# Power_Regulation.net
KiCad netlist of a schematic drawn in Altium Designer
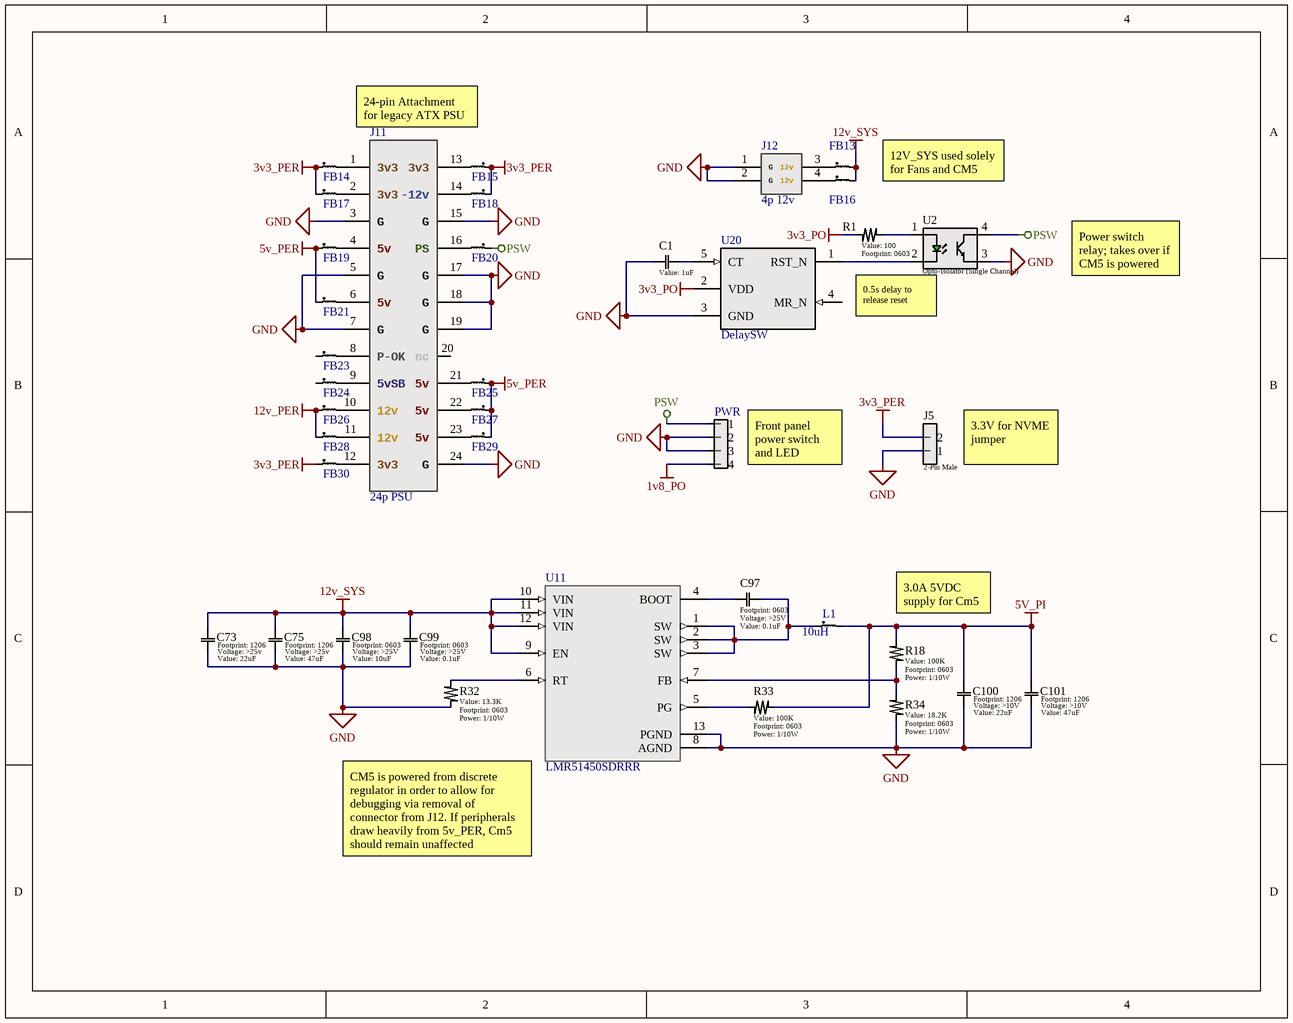
[diagram p0: Power_Regulation.SchDoc]

(export (version "E")
  (design (tool "Eeschema 10.0.6"))
  (components
    (comp (ref "C1")
      (value "1uF")
      (footprint "0603")
      (fields
        (field (name "VOLTAGE") "10V")
        (field (name "TOLERANCE") "10%")
        (field (name "Comment") "Generic Capacitor")
      )
      (libsource (lib "Capacitors") (part "Generic Capacitor"))
    )
    (comp (ref "C73")
      (value "22uF")
      (footprint "1206")
      (fields
        (field (name "VOLTAGE") ">25v")
        (field (name "TOLERANCE") "20%")
        (field (name "Comment") "Generic Capacitor")
      )
      (libsource (lib "Capacitors") (part "Generic Capacitor"))
    )
    (comp (ref "C75")
      (value "47uF")
      (footprint "1206")
      (fields
        (field (name "VOLTAGE") ">25v")
        (field (name "TOLERANCE") "20%")
        (field (name "Comment") "Generic Capacitor")
      )
      (libsource (lib "Capacitors") (part "Generic Capacitor"))
    )
    (comp (ref "C97")
      (value "0.1uF")
      (footprint "0603")
      (fields
        (field (name "VOLTAGE") ">25V")
        (field (name "TOLERANCE") "10%")
        (field (name "Comment") "Generic Capacitor")
      )
      (libsource (lib "Capacitors") (part "Generic Capacitor"))
    )
    (comp (ref "C98")
      (value "10uF")
      (footprint "0603")
      (fields
        (field (name "VOLTAGE") ">25V")
        (field (name "TOLERANCE") "10%")
        (field (name "Comment") "Generic Capacitor")
      )
      (libsource (lib "Capacitors") (part "Generic Capacitor"))
    )
    (comp (ref "C99")
      (value "0.1uF")
      (footprint "0603")
      (fields
        (field (name "VOLTAGE") ">25V")
        (field (name "TOLERANCE") "10%")
        (field (name "Comment") "Generic Capacitor")
      )
      (libsource (lib "Capacitors") (part "Generic Capacitor"))
    )
    (comp (ref "C100")
      (value "22uF")
      (footprint "1206")
      (fields
        (field (name "VOLTAGE") ">10V")
        (field (name "TOLERANCE") "20%")
        (field (name "Comment") "Generic Capacitor")
      )
      (libsource (lib "Capacitors") (part "Generic Capacitor"))
    )
    (comp (ref "C101")
      (value "47uF")
      (footprint "1206")
      (fields
        (field (name "VOLTAGE") ">10V")
        (field (name "TOLERANCE") "10%")
        (field (name "Comment") "Generic Capacitor")
      )
      (libsource (lib "Capacitors") (part "Generic Capacitor"))
    )
    (comp (ref "FB13")
      (value "1206 Ferrite")
      (footprint "1206")
      (description "160 Ohms @ 100MHz 1 Power, Signal Line Ferrite Bead 1206 (3216 Metric) 6A 18mOhm")
      (libsource (lib "Inductors") (part "HI1206T161R-10"))
    )
    (comp (ref "FB14")
      (value "1206 Ferrite")
      (footprint "1206")
      (description "160 Ohms @ 100MHz 1 Power, Signal Line Ferrite Bead 1206 (3216 Metric) 6A 18mOhm")
      (libsource (lib "Inductors") (part "HI1206T161R-10"))
    )
    (comp (ref "FB15")
      (value "1206 Ferrite")
      (footprint "1206")
      (description "160 Ohms @ 100MHz 1 Power, Signal Line Ferrite Bead 1206 (3216 Metric) 6A 18mOhm")
      (libsource (lib "") (part "HI1206T161R-10_1"))
    )
    (comp (ref "FB16")
      (value "1206 Ferrite")
      (footprint "1206")
      (description "160 Ohms @ 100MHz 1 Power, Signal Line Ferrite Bead 1206 (3216 Metric) 6A 18mOhm")
      (libsource (lib "Inductors") (part "HI1206T161R-10"))
    )
    (comp (ref "FB17")
      (value "1206 Ferrite")
      (footprint "1206")
      (description "160 Ohms @ 100MHz 1 Power, Signal Line Ferrite Bead 1206 (3216 Metric) 6A 18mOhm")
      (libsource (lib "Inductors") (part "HI1206T161R-10"))
    )
    (comp (ref "FB18")
      (value "1206 Ferrite")
      (footprint "1206")
      (description "160 Ohms @ 100MHz 1 Power, Signal Line Ferrite Bead 1206 (3216 Metric) 6A 18mOhm")
      (libsource (lib "") (part "HI1206T161R-10_1"))
    )
    (comp (ref "FB19")
      (value "1206 Ferrite")
      (footprint "1206")
      (description "160 Ohms @ 100MHz 1 Power, Signal Line Ferrite Bead 1206 (3216 Metric) 6A 18mOhm")
      (libsource (lib "Inductors") (part "HI1206T161R-10"))
    )
    (comp (ref "FB20")
      (value "1206 Ferrite")
      (footprint "1206")
      (description "160 Ohms @ 100MHz 1 Power, Signal Line Ferrite Bead 1206 (3216 Metric) 6A 18mOhm")
      (libsource (lib "") (part "HI1206T161R-10_1"))
    )
    (comp (ref "FB21")
      (value "1206 Ferrite")
      (footprint "1206")
      (description "160 Ohms @ 100MHz 1 Power, Signal Line Ferrite Bead 1206 (3216 Metric) 6A 18mOhm")
      (libsource (lib "Inductors") (part "HI1206T161R-10"))
    )
    (comp (ref "FB23")
      (value "1206 Ferrite")
      (footprint "1206")
      (description "160 Ohms @ 100MHz 1 Power, Signal Line Ferrite Bead 1206 (3216 Metric) 6A 18mOhm")
      (libsource (lib "Inductors") (part "HI1206T161R-10"))
    )
    (comp (ref "FB24")
      (value "1206 Ferrite")
      (footprint "1206")
      (description "160 Ohms @ 100MHz 1 Power, Signal Line Ferrite Bead 1206 (3216 Metric) 6A 18mOhm")
      (libsource (lib "Inductors") (part "HI1206T161R-10"))
    )
    (comp (ref "FB25")
      (value "1206 Ferrite")
      (footprint "1206")
      (description "160 Ohms @ 100MHz 1 Power, Signal Line Ferrite Bead 1206 (3216 Metric) 6A 18mOhm")
      (libsource (lib "") (part "HI1206T161R-10_1"))
    )
    (comp (ref "FB26")
      (value "1206 Ferrite")
      (footprint "1206")
      (description "160 Ohms @ 100MHz 1 Power, Signal Line Ferrite Bead 1206 (3216 Metric) 6A 18mOhm")
      (libsource (lib "Inductors") (part "HI1206T161R-10"))
    )
    (comp (ref "FB27")
      (value "1206 Ferrite")
      (footprint "1206")
      (description "160 Ohms @ 100MHz 1 Power, Signal Line Ferrite Bead 1206 (3216 Metric) 6A 18mOhm")
      (libsource (lib "") (part "HI1206T161R-10_1"))
    )
    (comp (ref "FB28")
      (value "1206 Ferrite")
      (footprint "1206")
      (description "160 Ohms @ 100MHz 1 Power, Signal Line Ferrite Bead 1206 (3216 Metric) 6A 18mOhm")
      (libsource (lib "Inductors") (part "HI1206T161R-10"))
    )
    (comp (ref "FB29")
      (value "1206 Ferrite")
      (footprint "1206")
      (description "160 Ohms @ 100MHz 1 Power, Signal Line Ferrite Bead 1206 (3216 Metric) 6A 18mOhm")
      (libsource (lib "") (part "HI1206T161R-10_1"))
    )
    (comp (ref "FB30")
      (value "1206 Ferrite")
      (footprint "1206")
      (description "160 Ohms @ 100MHz 1 Power, Signal Line Ferrite Bead 1206 (3216 Metric) 6A 18mOhm")
      (libsource (lib "Inductors") (part "HI1206T161R-10"))
    )
    (comp (ref "J5")
      (value "2-Pin Male")
      (footprint "0022057025")
      (description "Conn Shrouded Header (4 Sides) HDR 2 POS 2.5mm Solder RA Thru-Hole SPOX™ Bag")
      (libsource (lib "Connectors") (part "0022057025"))
    )
    (comp (ref "J11")
      (value "24p PSU")
      (footprint "CONN_442060007_MOL")
      (description "Connector Header Through Hole 24 position 0.165\" (4.20mm)")
      (libsource (lib "Connectors") (part "442060007"))
    )
    (comp (ref "J12")
      (value "4p 12v")
      (footprint "CON_39281043")
      (description "Connector Header Through Hole 4 position 0.165\" (4.20mm)")
      (libsource (lib "Connectors") (part "39281043"))
    )
    (comp (ref "L1")
      (value "10uH")
      (footprint "SMD 8.2x8.6mm")
      (description "5.1A 10uH ±20% 5.2A - Power Inductor")
      (fields
        (field (name "MANUFACTURER_PART_NUMBER") "IHLP3232DZER100M5A")
        (field (name "COPYRIGHT") "Copyright (C) 2023 Ultra Librarian. All rights reserved.")
      )
      (libsource (lib "Inductors") (part "IHLP3232DZER100M5A"))
    )
    (comp (ref "PWR")
      (value "4-Pin Male Header (0.100\" Pitch)")
      (footprint "TSW-104-07-T-S")
      (description "Connector Header Through Hole 4 position 0.100\" (2.54mm)")
      (libsource (lib "Connectors") (part "TSW-104-07-T-S"))
    )
    (comp (ref "R1")
      (value "100")
      (footprint "0603")
      (fields
        (field (name "TOLERANCE") "1%")
        (field (name "POWER") "1/10W")
        (field (name "Comment") "Generic Resistor")
      )
      (libsource (lib "Resistors") (part "Generic Resistor"))
    )
    (comp (ref "R18")
      (value "100K")
      (footprint "0603")
      (fields
        (field (name "TOLERANCE") "1%")
        (field (name "POWER") "1/10W")
        (field (name "Comment") "Generic Resistor")
      )
      (libsource (lib "Resistors") (part "Generic Resistor"))
    )
    (comp (ref "R32")
      (value "13.3K")
      (footprint "0603")
      (fields
        (field (name "TOLERANCE") "1%")
        (field (name "POWER") "1/10W")
        (field (name "Comment") "Generic Resistor")
      )
      (libsource (lib "Resistors") (part "Generic Resistor"))
    )
    (comp (ref "R33")
      (value "100K")
      (footprint "0603")
      (fields
        (field (name "TOLERANCE") "1%")
        (field (name "POWER") "1/10W")
        (field (name "Comment") "Generic Resistor")
      )
      (libsource (lib "Resistors") (part "Generic Resistor"))
    )
    (comp (ref "R34")
      (value "18.2K")
      (footprint "0603")
      (fields
        (field (name "TOLERANCE") "1%")
        (field (name "POWER") "1/10W")
        (field (name "Comment") "Generic Resistor")
      )
      (libsource (lib "Resistors") (part "Generic Resistor"))
    )
    (comp (ref "U2")
      (value "Opto-Isolator (Single Channel)")
      (footprint "4-SMD (7.62mm Gull-Wing) Opto-Transistor")
      (description "LTV Series Single Channel 80 V 5000 Vrms Transistor Output Optocoupler SMT-DIP-4")
      (fields
        (field (name "MANUFACTURER") "Vishay Lite-On")
        (field (name "MANUFACTURER PART NUMBER") "LTV-816S-TA1")
      )
      (libsource (lib "Switches") (part "LTV-816S"))
    )
    (comp (ref "U11")
      (value "LMR51450SDRRR")
      (footprint "WSON-12")
      (description "36-V, 5-A synchronous buck converter")
      (fields (field (name "MF") "Texas Instruments"))
      (libsource (lib "Regulators") (part "LMR51450SDRRR"))
    )
    (comp (ref "U20")
      (value "DelaySW")
      (footprint "TSOT-23-5")
      (description "Supervisor Open Drain or Open Collector 1 Channel SOT-23-5\r\n2.2V Threshold")
      (libsource (lib "Switches") (part "TPS3840DL22DBVR"))
    )
  )
  (nets
    (net (code "1") (name "1v8_PO") (class "Default")
      (node (ref "PWR") (pin "4") (pinfunction "4_4") (pintype "passive"))
    )
    (net (code "2") (name "3v3_PER") (class "Default")
      (node (ref "FB14") (pin "1") (pinfunction "1_1") (pintype "passive"))
      (node (ref "FB15") (pin "1") (pinfunction "1_1") (pintype "passive"))
      (node (ref "FB17") (pin "1") (pinfunction "1_1") (pintype "passive"))
      (node (ref "FB18") (pin "1") (pinfunction "1_1") (pintype "passive"))
      (node (ref "FB30") (pin "1") (pinfunction "1_1") (pintype "passive"))
      (node (ref "J5") (pin "2") (pinfunction "2_2") (pintype "passive"))
    )
    (net (code "3") (name "3v3_PO") (class "Default")
      (node (ref "R1") (pin "1") (pinfunction "1_1") (pintype "passive"))
      (node (ref "U20") (pin "2") (pinfunction "VDD_2") (pintype "power_in"))
    )
    (net (code "4") (name "5V_PI") (class "Default")
      (node (ref "C100") (pin "1") (pinfunction "1_1") (pintype "passive"))
      (node (ref "C101") (pin "1") (pinfunction "1_1") (pintype "passive"))
      (node (ref "L1") (pin "2") (pinfunction "2_2") (pintype "passive"))
      (node (ref "R18") (pin "2") (pinfunction "2_2") (pintype "passive"))
      (node (ref "R33") (pin "1") (pinfunction "1_1") (pintype "passive"))
    )
    (net (code "5") (name "5v_PER") (class "Default")
      (node (ref "FB19") (pin "1") (pinfunction "1_1") (pintype "passive"))
      (node (ref "FB21") (pin "1") (pinfunction "1_1") (pintype "passive"))
      (node (ref "FB25") (pin "1") (pinfunction "1_1") (pintype "passive"))
      (node (ref "FB27") (pin "1") (pinfunction "1_1") (pintype "passive"))
      (node (ref "FB29") (pin "1") (pinfunction "1_1") (pintype "passive"))
    )
    (net (code "6") (name "12v_PER") (class "Default")
      (node (ref "FB26") (pin "1") (pinfunction "1_1") (pintype "passive"))
      (node (ref "FB28") (pin "1") (pinfunction "1_1") (pintype "passive"))
    )
    (net (code "7") (name "12v_SYS") (class "Default")
      (node (ref "C73") (pin "1") (pinfunction "1_1") (pintype "passive"))
      (node (ref "C75") (pin "1") (pinfunction "1_1") (pintype "passive"))
      (node (ref "C98") (pin "1") (pinfunction "1_1") (pintype "passive"))
      (node (ref "C99") (pin "1") (pinfunction "1_1") (pintype "passive"))
      (node (ref "FB13") (pin "2") (pinfunction "2_2") (pintype "passive"))
      (node (ref "FB16") (pin "2") (pinfunction "2_2") (pintype "passive"))
      (node (ref "U11") (pin "10") (pinfunction "VIN_10") (pintype "input"))
      (node (ref "U11") (pin "11") (pinfunction "VIN_11") (pintype "input"))
      (node (ref "U11") (pin "12") (pinfunction "VIN_12") (pintype "input"))
      (node (ref "U11") (pin "9") (pinfunction "EN_9") (pintype "input"))
    )
    (net (code "8") (name "GND") (class "Default")
      (node (ref "C1") (pin "2") (pinfunction "2_2") (pintype "passive"))
      (node (ref "C100") (pin "2") (pinfunction "2_2") (pintype "passive"))
      (node (ref "C101") (pin "2") (pinfunction "2_2") (pintype "passive"))
      (node (ref "C73") (pin "2") (pinfunction "2_2") (pintype "passive"))
      (node (ref "C75") (pin "2") (pinfunction "2_2") (pintype "passive"))
      (node (ref "C98") (pin "2") (pinfunction "2_2") (pintype "passive"))
      (node (ref "C99") (pin "2") (pinfunction "2_2") (pintype "passive"))
      (node (ref "J11") (pin "15") (pinfunction "G_15") (pintype "passive"))
      (node (ref "J11") (pin "17") (pinfunction "G_17") (pintype "passive"))
      (node (ref "J11") (pin "18") (pinfunction "G_18") (pintype "passive"))
      (node (ref "J11") (pin "19") (pinfunction "G_19") (pintype "passive"))
      (node (ref "J11") (pin "24") (pinfunction "G_24") (pintype "passive"))
      (node (ref "J11") (pin "3") (pinfunction "G_3") (pintype "passive"))
      (node (ref "J11") (pin "5") (pinfunction "G_5") (pintype "passive"))
      (node (ref "J11") (pin "7") (pinfunction "G_7") (pintype "passive"))
      (node (ref "J12") (pin "1") (pinfunction "G_1") (pintype "passive"))
      (node (ref "J12") (pin "2") (pinfunction "G_2") (pintype "passive"))
      (node (ref "J5") (pin "1") (pinfunction "1_1") (pintype "passive"))
      (node (ref "PWR") (pin "2") (pinfunction "2_2") (pintype "passive"))
      (node (ref "PWR") (pin "3") (pinfunction "3_3") (pintype "passive"))
      (node (ref "R32") (pin "1") (pinfunction "1_1") (pintype "passive"))
      (node (ref "R34") (pin "1") (pinfunction "1_1") (pintype "passive"))
      (node (ref "U11") (pin "13") (pinfunction "PGND_13") (pintype "power_in"))
      (node (ref "U11") (pin "8") (pinfunction "AGND_8") (pintype "power_in"))
      (node (ref "U2") (pin "3") (pinfunction "3_3") (pintype "passive"))
      (node (ref "U20") (pin "3") (pinfunction "GND_3") (pintype "power_in"))
    )
    (net (code "9") (name "Net-(C97-Pad2)") (class "Default")
      (node (ref "C97") (pin "2") (pinfunction "2_2") (pintype "passive"))
      (node (ref "L1") (pin "1") (pinfunction "1_1") (pintype "passive"))
      (node (ref "U11") (pin "1") (pinfunction "SW_1") (pintype "output"))
      (node (ref "U11") (pin "2") (pinfunction "SW_2") (pintype "output"))
      (node (ref "U11") (pin "3") (pinfunction "SW_3") (pintype "output"))
    )
    (net (code "10") (name "Net-(FB13-Pad1)") (class "Default")
      (node (ref "FB13") (pin "1") (pinfunction "1_1") (pintype "passive"))
      (node (ref "J12") (pin "3") (pinfunction "12v_3") (pintype "passive"))
    )
    (net (code "11") (name "Net-(FB14-Pad2)") (class "Default")
      (node (ref "FB14") (pin "2") (pinfunction "2_2") (pintype "passive"))
      (node (ref "J11") (pin "1") (pinfunction "3v3_1") (pintype "passive"))
    )
    (net (code "12") (name "Net-(FB15-Pad2)") (class "Default")
      (node (ref "FB15") (pin "2") (pinfunction "2_2") (pintype "passive"))
      (node (ref "J11") (pin "13") (pinfunction "3v3_13") (pintype "passive"))
    )
    (net (code "13") (name "Net-(FB16-Pad1)") (class "Default")
      (node (ref "FB16") (pin "1") (pinfunction "1_1") (pintype "passive"))
      (node (ref "J12") (pin "4") (pinfunction "12v_4") (pintype "passive"))
    )
    (net (code "14") (name "Net-(FB17-Pad2)") (class "Default")
      (node (ref "FB17") (pin "2") (pinfunction "2_2") (pintype "passive"))
      (node (ref "J11") (pin "2") (pinfunction "3v3_2") (pintype "passive"))
    )
    (net (code "15") (name "Net-(FB19-Pad2)") (class "Default")
      (node (ref "FB19") (pin "2") (pinfunction "2_2") (pintype "passive"))
      (node (ref "J11") (pin "4") (pinfunction "5v_4") (pintype "passive"))
    )
    (net (code "16") (name "Net-(FB21-Pad2)") (class "Default")
      (node (ref "FB21") (pin "2") (pinfunction "2_2") (pintype "passive"))
      (node (ref "J11") (pin "6") (pinfunction "5v_6") (pintype "passive"))
    )
    (net (code "17") (name "Net-(FB25-Pad2)") (class "Default")
      (node (ref "FB25") (pin "2") (pinfunction "2_2") (pintype "passive"))
      (node (ref "J11") (pin "21") (pinfunction "5v_21") (pintype "passive"))
    )
    (net (code "18") (name "Net-(FB26-Pad2)") (class "Default")
      (node (ref "FB26") (pin "2") (pinfunction "2_2") (pintype "passive"))
      (node (ref "J11") (pin "10") (pinfunction "12v_10") (pintype "passive"))
    )
    (net (code "19") (name "Net-(FB27-Pad2)") (class "Default")
      (node (ref "FB27") (pin "2") (pinfunction "2_2") (pintype "passive"))
      (node (ref "J11") (pin "22") (pinfunction "5v_22") (pintype "passive"))
    )
    (net (code "20") (name "Net-(FB28-Pad2)") (class "Default")
      (node (ref "FB28") (pin "2") (pinfunction "2_2") (pintype "passive"))
      (node (ref "J11") (pin "11") (pinfunction "12v_11") (pintype "passive"))
    )
    (net (code "21") (name "Net-(FB29-Pad2)") (class "Default")
      (node (ref "FB29") (pin "2") (pinfunction "2_2") (pintype "passive"))
      (node (ref "J11") (pin "23") (pinfunction "5v_23") (pintype "passive"))
    )
    (net (code "22") (name "Net-(FB30-Pad2)") (class "Default")
      (node (ref "FB30") (pin "2") (pinfunction "2_2") (pintype "passive"))
      (node (ref "J11") (pin "12") (pinfunction "3v3_12") (pintype "passive"))
    )
    (net (code "23") (name "Net-(J11--12v)") (class "Default")
      (node (ref "FB18") (pin "2") (pinfunction "2_2") (pintype "passive"))
      (node (ref "J11") (pin "14") (pinfunction "-12v_14") (pintype "passive"))
    )
    (net (code "24") (name "Net-(J11-5vSB)") (class "Default")
      (node (ref "FB24") (pin "2") (pinfunction "2_2") (pintype "passive"))
      (node (ref "J11") (pin "9") (pinfunction "5vSB_9") (pintype "passive"))
    )
    (net (code "25") (name "Net-(J11-P-OK)") (class "Default")
      (node (ref "FB23") (pin "2") (pinfunction "2_2") (pintype "passive"))
      (node (ref "J11") (pin "8") (pinfunction "P-OK_8") (pintype "passive"))
    )
    (net (code "26") (name "Net-(J11-PS)") (class "Default")
      (node (ref "FB20") (pin "2") (pinfunction "2_2") (pintype "passive"))
      (node (ref "J11") (pin "16") (pinfunction "PS_16") (pintype "passive"))
    )
    (net (code "27") (name "Net-(R1-Pad2)") (class "Default")
      (node (ref "R1") (pin "2") (pinfunction "2_2") (pintype "passive"))
      (node (ref "U2") (pin "1") (pinfunction "1_1") (pintype "passive"))
    )
    (net (code "28") (name "Net-(U11-BOOT)") (class "Default")
      (node (ref "C97") (pin "1") (pinfunction "1_1") (pintype "passive"))
      (node (ref "U11") (pin "4") (pinfunction "BOOT_4") (pintype "passive"))
    )
    (net (code "29") (name "Net-(U11-FB)") (class "Default")
      (node (ref "R18") (pin "1") (pinfunction "1_1") (pintype "passive"))
      (node (ref "R34") (pin "2") (pinfunction "2_2") (pintype "passive"))
      (node (ref "U11") (pin "7") (pinfunction "FB_7") (pintype "input"))
    )
    (net (code "30") (name "Net-(U11-PG)") (class "Default")
      (node (ref "R33") (pin "2") (pinfunction "2_2") (pintype "passive"))
      (node (ref "U11") (pin "5") (pinfunction "PG_5") (pintype "output"))
    )
    (net (code "31") (name "Net-(U11-RT)") (class "Default")
      (node (ref "R32") (pin "2") (pinfunction "2_2") (pintype "passive"))
      (node (ref "U11") (pin "6") (pinfunction "RT_6") (pintype "input"))
    )
    (net (code "32") (name "Net-(U20-CT)") (class "Default")
      (node (ref "C1") (pin "1") (pinfunction "1_1") (pintype "passive"))
      (node (ref "U20") (pin "5") (pinfunction "CT_5") (pintype "input"))
    )
    (net (code "33") (name "Net-(U20-RST_N)") (class "Default")
      (node (ref "U2") (pin "2") (pinfunction "2_2") (pintype "passive"))
      (node (ref "U20") (pin "1") (pinfunction "RST_N_1") (pintype "open_collector"))
    )
    (net (code "34") (name "PSW") (class "Default")
      (node (ref "FB20") (pin "1") (pinfunction "1_1") (pintype "passive"))
      (node (ref "PWR") (pin "1") (pinfunction "1_1") (pintype "passive"))
      (node (ref "U2") (pin "4") (pinfunction "4_4") (pintype "passive"))
    )
    (net (code "35") (name "unconnected-(FB23-Pad1)") (class "Default")
      (node (ref "FB23") (pin "1") (pinfunction "1_1") (pintype "passive"))
    )
    (net (code "36") (name "unconnected-(FB24-Pad1)") (class "Default")
      (node (ref "FB24") (pin "1") (pinfunction "1_1") (pintype "passive"))
    )
    (net (code "37") (name "unconnected-(J11-nc-Pad20)") (class "Default")
      (node (ref "J11") (pin "20") (pinfunction "nc_20") (pintype "passive"))
    )
    (net (code "38") (name "unconnected-(U20-MR_N-Pad4)") (class "Default")
      (node (ref "U20") (pin "4") (pinfunction "MR_N_4") (pintype "input"))
    )
  )
)
